# audio_proto.net
KiCad netlist of a schematic drawn in EAGLE
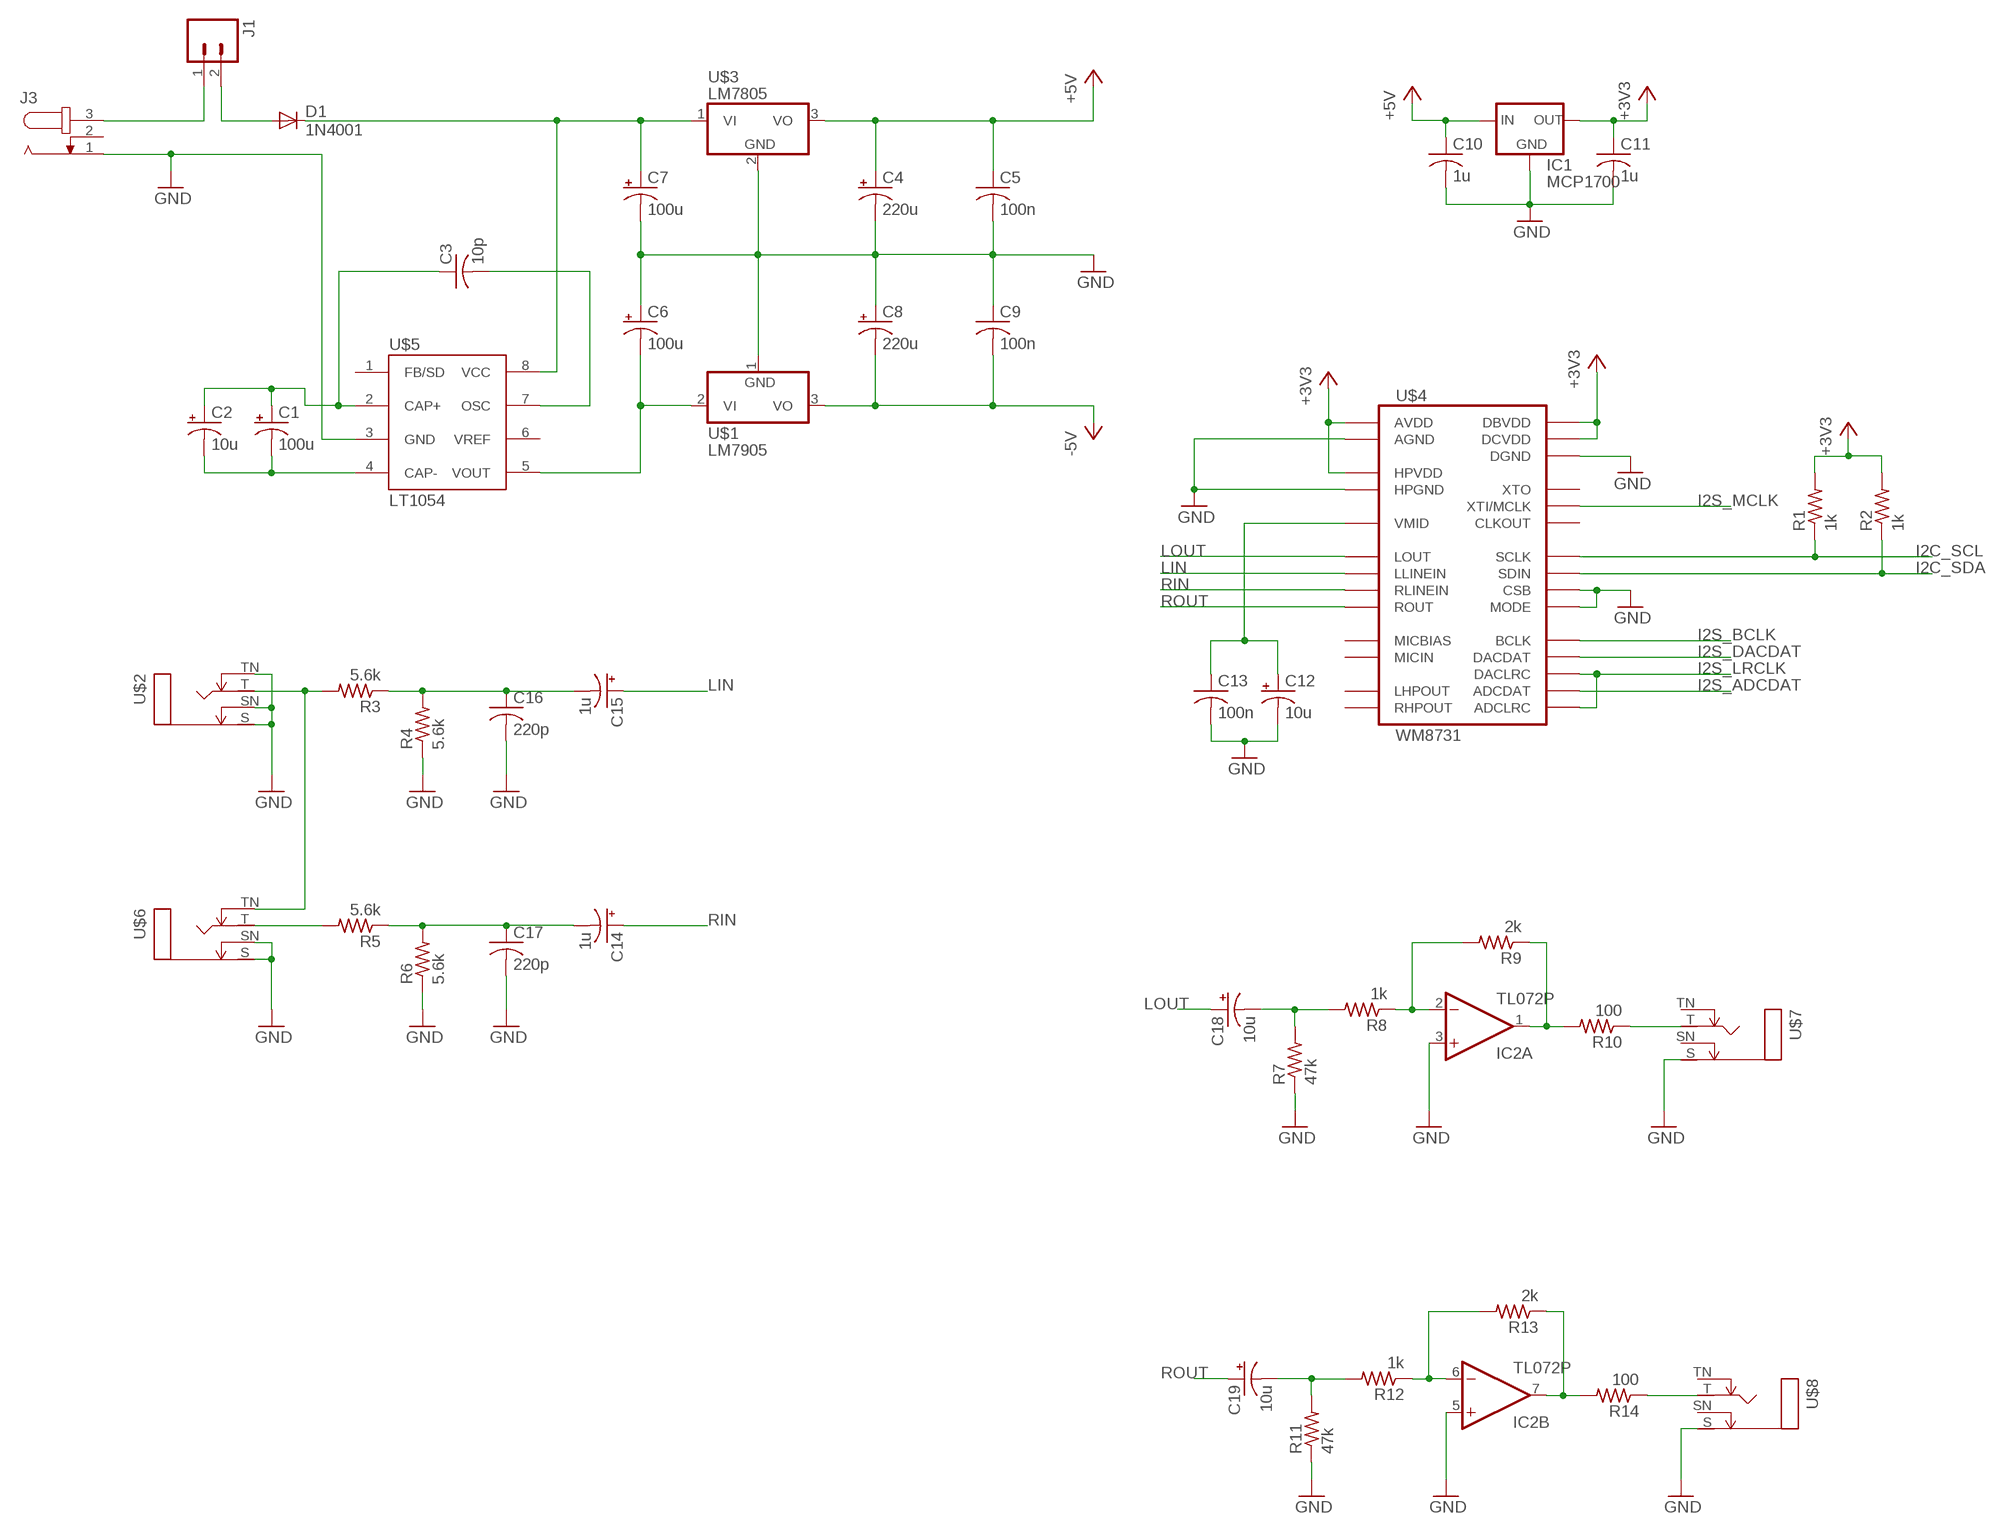
[diagram p0: schematic, sheet 1]

(export (version "E")
  (design (tool "Eeschema 10.0.6"))
  (components
    (comp (ref "C1")
      (value "100u")
      (footprint "eagle-import:E2,5-6")
      (libsource (lib "eagle-import") (part "CPOL-USE2.5-6"))
    )
    (comp (ref "C2")
      (value "10u")
      (footprint "eagle-import:E2,5-5")
      (libsource (lib "eagle-import") (part "CPOL-USE2.5-5"))
    )
    (comp (ref "C3")
      (value "10p")
      (footprint "eagle-import:C025-025X050")
      (libsource (lib "eagle-import") (part "C-US025-025X050"))
    )
    (comp (ref "C4")
      (value "220u")
      (footprint "eagle-import:E5-10,5")
      (libsource (lib "eagle-import") (part "CPOL-USE5-10.5"))
    )
    (comp (ref "C5")
      (value "100n")
      (footprint "eagle-import:C025-025X050")
      (libsource (lib "eagle-import") (part "C-US025-025X050"))
    )
    (comp (ref "C6")
      (value "100u")
      (footprint "eagle-import:E2,5-6")
      (libsource (lib "eagle-import") (part "CPOL-USE2.5-6"))
    )
    (comp (ref "C7")
      (value "100u")
      (footprint "eagle-import:E2,5-6")
      (libsource (lib "eagle-import") (part "CPOL-USE2.5-6"))
    )
    (comp (ref "C8")
      (value "220u")
      (footprint "eagle-import:E5-10,5")
      (libsource (lib "eagle-import") (part "CPOL-USE5-10.5"))
    )
    (comp (ref "C9")
      (value "100n")
      (footprint "eagle-import:C025-025X050")
      (libsource (lib "eagle-import") (part "C-US025-025X050"))
    )
    (comp (ref "C10")
      (value "1u")
      (footprint "eagle-import:C025-025X050")
      (libsource (lib "eagle-import") (part "C-US025-025X050"))
    )
    (comp (ref "C11")
      (value "1u")
      (footprint "eagle-import:C025-025X050")
      (libsource (lib "eagle-import") (part "C-US025-025X050"))
    )
    (comp (ref "C12")
      (value "10u")
      (footprint "eagle-import:E2,5-5")
      (libsource (lib "eagle-import") (part "CPOL-USE2.5-5"))
    )
    (comp (ref "C13")
      (value "100n")
      (footprint "eagle-import:C025-025X050")
      (libsource (lib "eagle-import") (part "C-US025-025X050"))
    )
    (comp (ref "C14")
      (value "1u")
      (footprint "eagle-import:E2,5-6")
      (libsource (lib "eagle-import") (part "CPOL-USE2.5-6"))
    )
    (comp (ref "C15")
      (value "1u")
      (footprint "eagle-import:E2,5-6")
      (libsource (lib "eagle-import") (part "CPOL-USE2.5-6"))
    )
    (comp (ref "C16")
      (value "220p")
      (footprint "eagle-import:C025-025X050")
      (libsource (lib "eagle-import") (part "C-US025-025X050"))
    )
    (comp (ref "C17")
      (value "220p")
      (footprint "eagle-import:C025-025X050")
      (libsource (lib "eagle-import") (part "C-US025-025X050"))
    )
    (comp (ref "C18")
      (value "10u")
      (footprint "eagle-import:E2,5-6")
      (libsource (lib "eagle-import") (part "CPOL-USE2.5-6"))
    )
    (comp (ref "C19")
      (value "10u")
      (footprint "eagle-import:E2,5-6")
      (libsource (lib "eagle-import") (part "CPOL-USE2.5-6"))
    )
    (comp (ref "D1")
      (value "1N4001")
      (footprint "eagle-import:DO41-10")
      (libsource (lib "eagle-import") (part "1N4004"))
    )
    (comp (ref "IC1")
      (value "MCP1700")
      (footprint "eagle-import:TO92-INLINE")
      (libsource (lib "eagle-import") (part "MCP1700INLINE"))
    )
    (comp (ref "IC2")
      (value "TL072P")
      (footprint "eagle-import:DIL08")
      (libsource (lib "eagle-import") (part "TL072P"))
    )
    (comp (ref "J1")
      (value "M02PTH")
      (footprint "eagle-import:1X02")
      (libsource (lib "eagle-import") (part "M02PTH"))
    )
    (comp (ref "J3")
      (value "JACK-PLUG2")
      (footprint "eagle-import:SPC4077")
      (libsource (lib "eagle-import") (part "JACK-PLUG2"))
    )
    (comp (ref "R1")
      (value "1k")
      (footprint "eagle-import:0207_10")
      (libsource (lib "eagle-import") (part "R-US_0207/10"))
    )
    (comp (ref "R2")
      (value "1k")
      (footprint "eagle-import:0207_10")
      (libsource (lib "eagle-import") (part "R-US_0207/10"))
    )
    (comp (ref "R3")
      (value "5.6k")
      (footprint "eagle-import:0207_10")
      (libsource (lib "eagle-import") (part "R-US_0207/10"))
    )
    (comp (ref "R4")
      (value "5.6k")
      (footprint "eagle-import:0207_10")
      (libsource (lib "eagle-import") (part "R-US_0207/10"))
    )
    (comp (ref "R5")
      (value "5.6k")
      (footprint "eagle-import:0207_10")
      (libsource (lib "eagle-import") (part "R-US_0207/10"))
    )
    (comp (ref "R6")
      (value "5.6k")
      (footprint "eagle-import:0207_10")
      (libsource (lib "eagle-import") (part "R-US_0207/10"))
    )
    (comp (ref "R7")
      (value "47k")
      (footprint "eagle-import:0207_10")
      (libsource (lib "eagle-import") (part "R-US_0207/10"))
    )
    (comp (ref "R8")
      (value "1k")
      (footprint "eagle-import:0207_10")
      (libsource (lib "eagle-import") (part "R-US_0207/10"))
    )
    (comp (ref "R9")
      (value "2k")
      (footprint "eagle-import:0207_10")
      (libsource (lib "eagle-import") (part "R-US_0207/10"))
    )
    (comp (ref "R10")
      (value "100")
      (footprint "eagle-import:0207_10")
      (libsource (lib "eagle-import") (part "R-US_0207/10"))
    )
    (comp (ref "R11")
      (value "47k")
      (footprint "eagle-import:0207_10")
      (libsource (lib "eagle-import") (part "R-US_0207/10"))
    )
    (comp (ref "R12")
      (value "1k")
      (footprint "eagle-import:0207_10")
      (libsource (lib "eagle-import") (part "R-US_0207/10"))
    )
    (comp (ref "R13")
      (value "2k")
      (footprint "eagle-import:0207_10")
      (libsource (lib "eagle-import") (part "R-US_0207/10"))
    )
    (comp (ref "R14")
      (value "100")
      (footprint "eagle-import:0207_10")
      (libsource (lib "eagle-import") (part "R-US_0207/10"))
    )
    (comp (ref "U$1")
      (value "LM7905")
      (footprint "eagle-import:TO220V")
      (libsource (lib "eagle-import") (part "LM7905"))
    )
    (comp (ref "U$2")
      (value "MONOJACKSW")
      (footprint "eagle-import:NMJ4HCD2")
      (libsource (lib "eagle-import") (part "MONOJACKSW"))
    )
    (comp (ref "U$3")
      (value "LM7805")
      (footprint "eagle-import:TO220V")
      (libsource (lib "eagle-import") (part "LM7805"))
    )
    (comp (ref "U$4")
      (value "WM8731")
      (footprint "eagle-import:DIL28-6")
      (libsource (lib "eagle-import") (part "WM8731"))
    )
    (comp (ref "U$5")
      (value "LT1054")
      (footprint "eagle-import:DIL08")
      (libsource (lib "eagle-import") (part "LT1054"))
    )
    (comp (ref "U$6")
      (value "MONOJACKSW")
      (footprint "eagle-import:NMJ4HCD2")
      (libsource (lib "eagle-import") (part "MONOJACKSW"))
    )
    (comp (ref "U$7")
      (value "MONOJACKSW")
      (footprint "eagle-import:NMJ4HCD2")
      (libsource (lib "eagle-import") (part "MONOJACKSW"))
    )
    (comp (ref "U$8")
      (value "MONOJACKSW")
      (footprint "eagle-import:NMJ4HCD2")
      (libsource (lib "eagle-import") (part "MONOJACKSW"))
    )
  )
  (nets
    (net (code "1") (name "+3V3") (class "Default")
      (node (ref "C11") (pin "1") (pinfunction "1_1") (pintype "passive"))
      (node (ref "IC1") (pin "3") (pinfunction "OUT_3") (pintype "passive"))
      (node (ref "R1") (pin "2") (pinfunction "2_2") (pintype "passive"))
      (node (ref "R2") (pin "2") (pinfunction "2_2") (pintype "passive"))
      (node (ref "U$4") (pin "1") (pinfunction "DBVDD_1") (pintype "power_in"))
      (node (ref "U$4") (pin "14") (pinfunction "AVDD_14") (pintype "power_in"))
      (node (ref "U$4") (pin "27") (pinfunction "DCVDD_27") (pintype "power_in"))
      (node (ref "U$4") (pin "8") (pinfunction "HPVDD_8") (pintype "power_in"))
    )
    (net (code "2") (name "+5V") (class "Default")
      (node (ref "C10") (pin "1") (pinfunction "1_1") (pintype "passive"))
      (node (ref "C4") (pin "+") (pinfunction "+_+") (pintype "passive"))
      (node (ref "C5") (pin "1") (pinfunction "1_1") (pintype "passive"))
      (node (ref "IC1") (pin "2") (pinfunction "IN_2") (pintype "input"))
      (node (ref "U$3") (pin "3") (pinfunction "VO_3") (pintype "passive"))
    )
    (net (code "3") (name "-5V") (class "Default")
      (node (ref "C8") (pin "-") (pinfunction "-_-") (pintype "passive"))
      (node (ref "C9") (pin "2") (pinfunction "2_2") (pintype "passive"))
      (node (ref "U$1") (pin "3") (pinfunction "VO_3") (pintype "passive"))
    )
    (net (code "4") (name "/I2C_SCL") (class "Default")
      (node (ref "R1") (pin "1") (pinfunction "1_1") (pintype "passive"))
      (node (ref "U$4") (pin "24") (pinfunction "SCLK_24") (pintype "input"))
    )
    (net (code "5") (name "/I2C_SDA") (class "Default")
      (node (ref "R2") (pin "1") (pinfunction "1_1") (pintype "passive"))
      (node (ref "U$4") (pin "23") (pinfunction "SDIN_23") (pintype "bidirectional"))
    )
    (net (code "6") (name "/I2S_ADCDAT") (class "Default")
      (node (ref "U$4") (pin "6") (pinfunction "ADCDAT_6") (pintype "output"))
    )
    (net (code "7") (name "/I2S_BCLK") (class "Default")
      (node (ref "U$4") (pin "3") (pinfunction "BCLK_3") (pintype "bidirectional"))
    )
    (net (code "8") (name "/I2S_DACDAT") (class "Default")
      (node (ref "U$4") (pin "4") (pinfunction "DACDAT_4") (pintype "input"))
    )
    (net (code "9") (name "/I2S_LRCLK") (class "Default")
      (node (ref "U$4") (pin "5") (pinfunction "DACLRC_5") (pintype "bidirectional"))
      (node (ref "U$4") (pin "7") (pinfunction "ADCLRC_7") (pintype "bidirectional"))
    )
    (net (code "10") (name "/I2S_MCLK") (class "Default")
      (node (ref "U$4") (pin "25") (pinfunction "XTI/MCLK_25") (pintype "input"))
    )
    (net (code "11") (name "/LIN") (class "Default")
      (node (ref "C15") (pin "+") (pinfunction "+_+") (pintype "passive"))
      (node (ref "U$4") (pin "20") (pinfunction "LLINEIN_20") (pintype "input"))
    )
    (net (code "12") (name "/LOUT") (class "Default")
      (node (ref "C18") (pin "+") (pinfunction "+_+") (pintype "passive"))
      (node (ref "U$4") (pin "12") (pinfunction "LOUT_12") (pintype "output"))
    )
    (net (code "13") (name "/RIN") (class "Default")
      (node (ref "C14") (pin "+") (pinfunction "+_+") (pintype "passive"))
      (node (ref "U$4") (pin "19") (pinfunction "RLINEIN_19") (pintype "input"))
    )
    (net (code "14") (name "/ROUT") (class "Default")
      (node (ref "C19") (pin "+") (pinfunction "+_+") (pintype "passive"))
      (node (ref "U$4") (pin "13") (pinfunction "ROUT_13") (pintype "output"))
    )
    (net (code "15") (name "GND") (class "Default")
      (node (ref "C10") (pin "2") (pinfunction "2_2") (pintype "passive"))
      (node (ref "C11") (pin "2") (pinfunction "2_2") (pintype "passive"))
      (node (ref "C12") (pin "-") (pinfunction "-_-") (pintype "passive"))
      (node (ref "C13") (pin "2") (pinfunction "2_2") (pintype "passive"))
      (node (ref "C16") (pin "2") (pinfunction "2_2") (pintype "passive"))
      (node (ref "C17") (pin "2") (pinfunction "2_2") (pintype "passive"))
      (node (ref "C4") (pin "-") (pinfunction "-_-") (pintype "passive"))
      (node (ref "C5") (pin "2") (pinfunction "2_2") (pintype "passive"))
      (node (ref "C6") (pin "+") (pinfunction "+_+") (pintype "passive"))
      (node (ref "C7") (pin "-") (pinfunction "-_-") (pintype "passive"))
      (node (ref "C8") (pin "+") (pinfunction "+_+") (pintype "passive"))
      (node (ref "C9") (pin "1") (pinfunction "1_1") (pintype "passive"))
      (node (ref "IC1") (pin "1") (pinfunction "GND_1") (pintype "input"))
      (node (ref "IC2") (pin "3") (pinfunction "+IN_3") (pintype "input"))
      (node (ref "IC2") (pin "5") (pinfunction "+IN_5") (pintype "input"))
      (node (ref "J3") (pin "1") (pinfunction "1_1") (pintype "passive"))
      (node (ref "R11") (pin "1") (pinfunction "1_1") (pintype "passive"))
      (node (ref "R4") (pin "1") (pinfunction "1_1") (pintype "passive"))
      (node (ref "R6") (pin "1") (pinfunction "1_1") (pintype "passive"))
      (node (ref "R7") (pin "1") (pinfunction "1_1") (pintype "passive"))
      (node (ref "U$1") (pin "1") (pinfunction "GND_1") (pintype "passive"))
      (node (ref "U$2") (pin "S") (pinfunction "S_S") (pintype "passive"))
      (node (ref "U$2") (pin "SN") (pinfunction "SN_SN") (pintype "passive"))
      (node (ref "U$2") (pin "TN") (pinfunction "TN_TN") (pintype "passive"))
      (node (ref "U$3") (pin "2") (pinfunction "GND_2") (pintype "passive"))
      (node (ref "U$4") (pin "11") (pinfunction "HPGND_11") (pintype "power_in"))
      (node (ref "U$4") (pin "15") (pinfunction "AGND_15") (pintype "power_in"))
      (node (ref "U$4") (pin "21") (pinfunction "MODE_21") (pintype "input"))
      (node (ref "U$4") (pin "22") (pinfunction "CSB_22") (pintype "input"))
      (node (ref "U$4") (pin "28") (pinfunction "DGND_28") (pintype "power_in"))
      (node (ref "U$5") (pin "3") (pinfunction "GND_3") (pintype "power_in"))
      (node (ref "U$6") (pin "S") (pinfunction "S_S") (pintype "passive"))
      (node (ref "U$6") (pin "SN") (pinfunction "SN_SN") (pintype "passive"))
      (node (ref "U$7") (pin "S") (pinfunction "S_S") (pintype "passive"))
      (node (ref "U$8") (pin "S") (pinfunction "S_S") (pintype "passive"))
    )
    (net (code "16") (name "Net-(C14-Pad-)") (class "Default")
      (node (ref "C14") (pin "-") (pinfunction "-_-") (pintype "passive"))
      (node (ref "C17") (pin "1") (pinfunction "1_1") (pintype "passive"))
      (node (ref "R5") (pin "1") (pinfunction "1_1") (pintype "passive"))
      (node (ref "R6") (pin "2") (pinfunction "2_2") (pintype "passive"))
    )
    (net (code "17") (name "Net-(C15-Pad-)") (class "Default")
      (node (ref "C15") (pin "-") (pinfunction "-_-") (pintype "passive"))
      (node (ref "C16") (pin "1") (pinfunction "1_1") (pintype "passive"))
      (node (ref "R3") (pin "1") (pinfunction "1_1") (pintype "passive"))
      (node (ref "R4") (pin "2") (pinfunction "2_2") (pintype "passive"))
    )
    (net (code "18") (name "Net-(C18-Pad-)") (class "Default")
      (node (ref "C18") (pin "-") (pinfunction "-_-") (pintype "passive"))
      (node (ref "R7") (pin "2") (pinfunction "2_2") (pintype "passive"))
      (node (ref "R8") (pin "2") (pinfunction "2_2") (pintype "passive"))
    )
    (net (code "19") (name "Net-(C19-Pad-)") (class "Default")
      (node (ref "C19") (pin "-") (pinfunction "-_-") (pintype "passive"))
      (node (ref "R11") (pin "2") (pinfunction "2_2") (pintype "passive"))
      (node (ref "R12") (pin "2") (pinfunction "2_2") (pintype "passive"))
    )
    (net (code "20") (name "Net-(D1-PadA)") (class "Default")
      (node (ref "D1") (pin "A") (pinfunction "A_A") (pintype "passive"))
      (node (ref "J1") (pin "2") (pinfunction "2_2") (pintype "passive"))
    )
    (net (code "21") (name "Net-(IC2A--IN)") (class "Default")
      (node (ref "IC2") (pin "2") (pinfunction "-IN_2") (pintype "input"))
      (node (ref "R8") (pin "1") (pinfunction "1_1") (pintype "passive"))
      (node (ref "R9") (pin "2") (pinfunction "2_2") (pintype "passive"))
    )
    (net (code "22") (name "Net-(IC2A-OUT)") (class "Default")
      (node (ref "IC2") (pin "1") (pinfunction "OUT_1") (pintype "output"))
      (node (ref "R10") (pin "2") (pinfunction "2_2") (pintype "passive"))
      (node (ref "R9") (pin "1") (pinfunction "1_1") (pintype "passive"))
    )
    (net (code "23") (name "Net-(IC2B--IN)") (class "Default")
      (node (ref "IC2") (pin "6") (pinfunction "-IN_6") (pintype "input"))
      (node (ref "R12") (pin "1") (pinfunction "1_1") (pintype "passive"))
      (node (ref "R13") (pin "2") (pinfunction "2_2") (pintype "passive"))
    )
    (net (code "24") (name "Net-(IC2B-OUT)") (class "Default")
      (node (ref "IC2") (pin "7") (pinfunction "OUT_7") (pintype "output"))
      (node (ref "R13") (pin "1") (pinfunction "1_1") (pintype "passive"))
      (node (ref "R14") (pin "2") (pinfunction "2_2") (pintype "passive"))
    )
    (net (code "25") (name "Net-(J1-Pad1)") (class "Default")
      (node (ref "J1") (pin "1") (pinfunction "1_1") (pintype "passive"))
      (node (ref "J3") (pin "3") (pinfunction "3_3") (pintype "passive"))
    )
    (net (code "26") (name "Net-(R3-Pad2)") (class "Default")
      (node (ref "R3") (pin "2") (pinfunction "2_2") (pintype "passive"))
      (node (ref "U$2") (pin "T") (pinfunction "T_T") (pintype "passive"))
      (node (ref "U$6") (pin "TN") (pinfunction "TN_TN") (pintype "passive"))
    )
    (net (code "27") (name "Net-(R5-Pad2)") (class "Default")
      (node (ref "R5") (pin "2") (pinfunction "2_2") (pintype "passive"))
      (node (ref "U$6") (pin "T") (pinfunction "T_T") (pintype "passive"))
    )
    (net (code "28") (name "Net-(R10-Pad1)") (class "Default")
      (node (ref "R10") (pin "1") (pinfunction "1_1") (pintype "passive"))
      (node (ref "U$7") (pin "T") (pinfunction "T_T") (pintype "passive"))
    )
    (net (code "29") (name "Net-(R14-Pad1)") (class "Default")
      (node (ref "R14") (pin "1") (pinfunction "1_1") (pintype "passive"))
      (node (ref "U$8") (pin "T") (pinfunction "T_T") (pintype "passive"))
    )
    (net (code "30") (name "Net-(U$1-VI)") (class "Default")
      (node (ref "C6") (pin "-") (pinfunction "-_-") (pintype "passive"))
      (node (ref "U$1") (pin "2") (pinfunction "VI_2") (pintype "input"))
      (node (ref "U$5") (pin "5") (pinfunction "VOUT_5") (pintype "output"))
    )
    (net (code "31") (name "Net-(U$3-VI)") (class "Default")
      (node (ref "C7") (pin "+") (pinfunction "+_+") (pintype "passive"))
      (node (ref "D1") (pin "C") (pinfunction "C_C") (pintype "passive"))
      (node (ref "U$3") (pin "1") (pinfunction "VI_1") (pintype "input"))
      (node (ref "U$5") (pin "8") (pinfunction "VCC_8") (pintype "power_in"))
    )
    (net (code "32") (name "Net-(U$4-VMID)") (class "Default")
      (node (ref "C12") (pin "+") (pinfunction "+_+") (pintype "passive"))
      (node (ref "C13") (pin "1") (pinfunction "1_1") (pintype "passive"))
      (node (ref "U$4") (pin "16") (pinfunction "VMID_16") (pintype "output"))
    )
    (net (code "33") (name "Net-(U$5-CAP+)") (class "Default")
      (node (ref "C1") (pin "+") (pinfunction "+_+") (pintype "passive"))
      (node (ref "C2") (pin "+") (pinfunction "+_+") (pintype "passive"))
      (node (ref "C3") (pin "1") (pinfunction "1_1") (pintype "passive"))
      (node (ref "U$5") (pin "2") (pinfunction "CAP+_2") (pintype "input"))
    )
    (net (code "34") (name "Net-(U$5-CAP-)") (class "Default")
      (node (ref "C1") (pin "-") (pinfunction "-_-") (pintype "passive"))
      (node (ref "C2") (pin "-") (pinfunction "-_-") (pintype "passive"))
      (node (ref "U$5") (pin "4") (pinfunction "CAP-_4") (pintype "input"))
    )
    (net (code "35") (name "Net-(U$5-OSC)") (class "Default")
      (node (ref "C3") (pin "2") (pinfunction "2_2") (pintype "passive"))
      (node (ref "U$5") (pin "7") (pinfunction "OSC_7") (pintype "input"))
    )
    (net (code "36") (name "unconnected-(J3-Pad2)") (class "Default")
      (node (ref "J3") (pin "2") (pinfunction "2_2") (pintype "passive"))
    )
    (net (code "37") (name "unconnected-(U$4-CLKOUT-Pad2)") (class "Default")
      (node (ref "U$4") (pin "2") (pinfunction "CLKOUT_2") (pintype "output"))
    )
    (net (code "38") (name "unconnected-(U$4-LHPOUT-Pad9)") (class "Default")
      (node (ref "U$4") (pin "9") (pinfunction "LHPOUT_9") (pintype "output"))
    )
    (net (code "39") (name "unconnected-(U$4-MICBIAS-Pad17)") (class "Default")
      (node (ref "U$4") (pin "17") (pinfunction "MICBIAS_17") (pintype "output"))
    )
    (net (code "40") (name "unconnected-(U$4-MICIN-Pad18)") (class "Default")
      (node (ref "U$4") (pin "18") (pinfunction "MICIN_18") (pintype "input"))
    )
    (net (code "41") (name "unconnected-(U$4-RHPOUT-Pad10)") (class "Default")
      (node (ref "U$4") (pin "10") (pinfunction "RHPOUT_10") (pintype "output"))
    )
    (net (code "42") (name "unconnected-(U$4-XTO-Pad26)") (class "Default")
      (node (ref "U$4") (pin "26") (pinfunction "XTO_26") (pintype "output"))
    )
    (net (code "43") (name "unconnected-(U$5-FB{slash}SD-Pad1)") (class "Default")
      (node (ref "U$5") (pin "1") (pinfunction "FB/SD_1") (pintype "input"))
    )
    (net (code "44") (name "unconnected-(U$5-VREF-Pad6)") (class "Default")
      (node (ref "U$5") (pin "6") (pinfunction "VREF_6") (pintype "output"))
    )
    (net (code "45") (name "unconnected-(U$7-PadSN)") (class "Default")
      (node (ref "U$7") (pin "SN") (pinfunction "SN_SN") (pintype "passive"))
    )
    (net (code "46") (name "unconnected-(U$7-PadTN)") (class "Default")
      (node (ref "U$7") (pin "TN") (pinfunction "TN_TN") (pintype "passive"))
    )
    (net (code "47") (name "unconnected-(U$8-PadSN)") (class "Default")
      (node (ref "U$8") (pin "SN") (pinfunction "SN_SN") (pintype "passive"))
    )
    (net (code "48") (name "unconnected-(U$8-PadTN)") (class "Default")
      (node (ref "U$8") (pin "TN") (pinfunction "TN_TN") (pintype "passive"))
    )
  )
)
